# Power_supply.net
KiCad netlist of a schematic drawn in Altium Designer
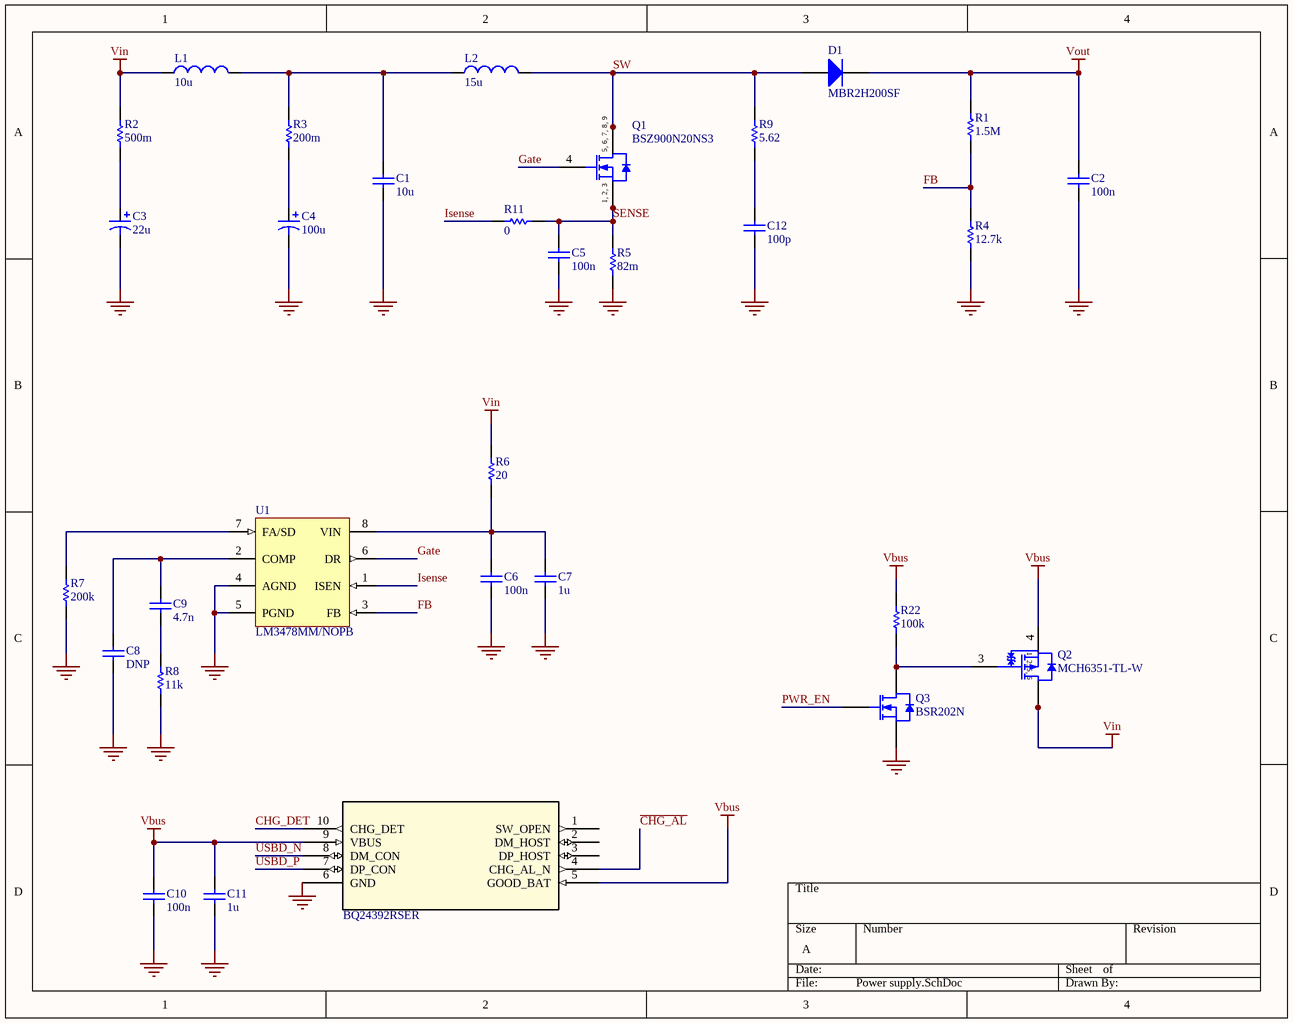
[diagram p0: Power supply.SchDoc]

(export (version "E")
  (design (tool "Eeschema 10.0.6"))
  (components
    (comp (ref "C1")
      (value "10u")
      (footprint "CAPC1206(3216)190_N")
      (description "CAP CER 10UF 25V X7R 1206")
      (fields
        (field (name "MANUFACTURER") "TDK Corporation")
        (field (name "MANUFACTURER PART NUMBER") "C3216X7R1E106K160AB")
      )
      (libsource (lib "Misc Caps") (part "C3216X7R1E106K160AB"))
    )
    (comp (ref "C2")
      (value "100n")
      (footprint "CAPC1812(4532)230_N")
      (fields
        (field (name "MANUFACTURER") "KEMET")
        (field (name "MANUFACTURER PART NUMBER") "C1812C104J2GACAUTO")
        (field (name "TOLERANCE") "5%")
      )
      (libsource (lib "Misc Caps") (part "C1812C104J2GACAUTO"))
    )
    (comp (ref "C3")
      (value "22u")
      (footprint "KEMET A")
      (description "CAP TANT POLY 22UF 6.3V 1206")
      (libsource (lib "Misc Caps") (part "T520A226M006ATE100"))
    )
    (comp (ref "C4")
      (value "100u")
      (footprint "KEMET A")
      (description "POLY TA SMD 3216 100UF 6.3V 20%")
      (libsource (lib "Misc Caps") (part "T520A107M006ATE045"))
    )
    (comp (ref "C5")
      (value "100n")
      (footprint "CAPC0603(1608)100_N")
      (description "CAP CER 0.1UF 10V X7R 0603")
      (fields
        (field (name "MANUFACTURER") "KEMET")
        (field (name "MANUFACTURER PART NUMBER") "C0603C104K8RACTU")
      )
      (libsource (lib "0603 Caps") (part "C0603C104K8RACTU"))
    )
    (comp (ref "C6")
      (value "100n")
      (footprint "CAPC0402(1005)33_N")
      (description "CAP CER 0.1UF 25V X7R 0402")
      (fields
        (field (name "MANUFACTURER") "Yageo")
        (field (name "MANUFACTURER PART NUMBER") "CC0402KRX7R8BB104")
      )
      (libsource (lib "0402 Caps") (part "CC0402KRX7R8BB104"))
    )
    (comp (ref "C7")
      (value "1u")
      (footprint "CAPC0402(1005)33_N")
      (description "CAP CER 1UF 25V X5R 0402")
      (libsource (lib "0402 Caps") (part "CGB2A1X5R1E105K033BC"))
    )
    (comp (ref "C8")
      (value "DNP")
      (footprint "CAPC0603(1608)100_N")
      (libsource (lib "0402 Caps") (part "0402 DNP JUMPER"))
    )
    (comp (ref "C9")
      (value "4.7n")
      (footprint "CAPC0603(1608)100_N")
      (description "CAP CER 4700PF 50V C0G 0603")
      (libsource (lib "0603 Caps") (part "C1608C0G1H472J080AA"))
    )
    (comp (ref "C10")
      (value "100n")
      (footprint "CAPC0402(1005)33_N")
      (description "CAP CER 0.1UF 25V X7R 0402")
      (fields
        (field (name "MANUFACTURER") "Yageo")
        (field (name "MANUFACTURER PART NUMBER") "CC0402KRX7R8BB104")
      )
      (libsource (lib "0402 Caps") (part "CC0402KRX7R8BB104"))
    )
    (comp (ref "C11")
      (value "1u")
      (footprint "CAPC0402(1005)33_N")
      (description "CAP CER 1UF 25V X5R 0402")
      (libsource (lib "0402 Caps") (part "CGB2A1X5R1E105K033BC"))
    )
    (comp (ref "C12")
      (value "100p")
      (footprint "CAPC0603(1608)100_N")
      (description "CAP CER 100PF 250V C0G/NP0 0603")
      (fields
        (field (name "MANUFACTURER") "KEMET")
        (field (name "MANUFACTURER PART NUMBER") "C0603C101JAGACTU")
      )
      (libsource (lib "0603 Caps") (part "C0603C101JAGACTU"))
    )
    (comp (ref "D1")
      (value "MBR2H200SF")
      (footprint "SOD-123FL")
      (description "DIODE SCHOTTKY 200V 2A SOD123")
      (fields
        (field (name "MANUFACTURER") "ON Semiconductor")
        (field (name "MANUFACTURER PART NUMBER") "MBR2H200SFT3G")
      )
      (libsource (lib "Discretes") (part "MBR2H200SF"))
    )
    (comp (ref "L1")
      (value "10u")
      (footprint "VLS6045EX")
      (description "FIXED IND 10UH 3.4A 61 MOHM SMD")
      (libsource (lib "Magnetics") (part "VLS6045EX-100M"))
    )
    (comp (ref "L2")
      (value "15u")
      (footprint "SRU8043")
      (description "FIXED IND 15UH 2.7A 46 MOHM SMD")
      (fields (field (name "MANUFACTURER") "Bourns") (field (name "MANUFACTURER PART NUMBER") "SRU8043-150Y"))
      (libsource (lib "Magnetics") (part "SRU8043-150Y"))
    )
    (comp (ref "Q1")
      (value "BSZ900N20NS3")
      (footprint "PG-TSDSON-8")
      (description "Trans MOSFET N-CH 200V 15.2A 8-Pin TSDSON")
      (fields
        (field (name "MANUFACTURER") "Infineon")
        (field (name "MANUFACTURER PART NUMBER") "BSZ900N20NS3GATMA1")
      )
      (libsource (lib "Discretes") (part "BSZ900N20NS3GATMA1"))
    )
    (comp (ref "Q2")
      (value "MCH6351-TL-W")
      (footprint "SOT23-6P65_210X90L25X32")
      (description "MOSFET PCH 1.8V DRIVE SERIES")
      (fields (field (name "MANUFACTURER") "ON Semiconductor"))
      (libsource (lib "Discretes") (part "MCH6351-TL-W"))
    )
    (comp (ref "Q3")
      (value "BSR202N")
      (footprint "INF-PG-SC59_N")
      (description "Trans MOSFET N-CH 20V 3.8A 3-Pin SC-59 T/R")
      (fields
        (field (name "MANUFACTURER") "Infineon")
        (field (name "MANUFACTURER PART NUMBER") "BSR202NL6327HTSA1")
      )
      (libsource (lib "Discretes") (part "BSR202N"))
    )
    (comp (ref "R1")
      (value "1.5M")
      (footprint "RESC0805(2012)_N")
      (description "RES SMD 1.5M OHM 0.1% 1/10W 0805")
      (fields
        (field (name "MANUFACTURER") "TE Connectivity Passive Product")
        (field (name "MANUFACTURER PART NUMBER") "CPF0805B1M5E1")
      )
      (libsource (lib "0805 Resistors") (part "CPF0805B1M5E1"))
    )
    (comp (ref "R2")
      (value "500m")
      (footprint "RESC0402(1005)_N")
      (description "RES 0.5 OHM 1% 1/16W 0402")
      (fields
        (field (name "MANUFACTURER") "Yageo")
        (field (name "MANUFACTURER PART NUMBER") "RC0402FR-071RL")
      )
      (libsource (lib "0402 Resistors") (part "RL0402FR-070R5L"))
    )
    (comp (ref "R3")
      (value "200m")
      (footprint "RESC0402(1005)_N")
      (description "RES 0.22 OHM 1% 1/16W 0402")
      (fields
        (field (name "MANUFACTURER") "Yageo")
        (field (name "MANUFACTURER PART NUMBER") "RC0402FR-071RL")
      )
      (libsource (lib "0402 Resistors") (part "RL0402FR-070R22L"))
    )
    (comp (ref "R4")
      (value "12.7k")
      (footprint "RESC0805(2012)_N")
      (description "RES SMD 12.7K OHM 0.1% 1/8W 0805")
      (fields
        (field (name "MANUFACTURER") "Yageo")
        (field (name "MANUFACTURER PART NUMBER") "RT0805BRD0712K7L")
      )
      (libsource (lib "0805 Resistors") (part "RT0805BRD0712K7L"))
    )
    (comp (ref "R5")
      (value "82m")
      (footprint "RESC0603(1608)_N")
      (fields
        (field (name "MANUFACTURER") "Panasonic")
        (field (name "MANUFACTURER PART NUMBER") "ERJ-3BWFR082V")
        (field (name "TOLERANCE") "1%")
      )
      (libsource (lib "0603 Resistors") (part "ERJ-3BWFR082V"))
    )
    (comp (ref "R6")
      (value "20")
      (footprint "RESC0402(1005)_N")
      (description "RES SMD 20 OHM 1% 1/16W 0402")
      (fields
        (field (name "MANUFACTURER") "Yageo")
        (field (name "MANUFACTURER PART NUMBER") "RC0402FR-0720RL")
      )
      (libsource (lib "0402 Resistors") (part "RC0402FR-0720RL"))
    )
    (comp (ref "R7")
      (value "200k")
      (footprint "RESC0402(1005)_N")
      (description "RES SMD 200K OHM 1% 1/16W 0402")
      (fields
        (field (name "MANUFACTURER") "Yageo")
        (field (name "MANUFACTURER PART NUMBER") "RC0402FR-07200KL")
      )
      (libsource (lib "0402 Resistors") (part "RC0402FR-07200KL"))
    )
    (comp (ref "R8")
      (value "11k")
      (footprint "RESC0402(1005)_N")
      (description "RES SMD 11K OHM 1% 1/16W 0402")
      (fields
        (field (name "MANUFACTURER") "Yageo")
        (field (name "MANUFACTURER PART NUMBER") "RC0402FR-0711KL")
      )
      (libsource (lib "0402 Resistors") (part "RC0402FR-0711KL"))
    )
    (comp (ref "R9")
      (value "5.62")
      (footprint "RESC0603(1608)_N")
      (description "RES SMD 5.62 OHM 1% 1/10W 0603")
      (fields
        (field (name "MANUFACTURER") "Vishay Dale")
        (field (name "MANUFACTURER PART NUMBER") "CRCW06035R62FKEA")
      )
      (libsource (lib "0603 Resistors") (part "CRCW06035R62FKEA"))
    )
    (comp (ref "R11")
      (value "0")
      (footprint "RESC0402(1005)_N")
      (description "RES SMD 0 OHM JUMPER 1/16W 0402")
      (fields
        (field (name "MANUFACTURER") "Yageo")
        (field (name "MANUFACTURER PART NUMBER") "RC0402FR-070RL")
      )
      (libsource (lib "0402 Resistors") (part "RC0402FR-070RL"))
    )
    (comp (ref "R22")
      (value "100k")
      (footprint "RESC0402(1005)_N")
      (description "RES SMD 100K OHM 1% 1/16W 0402")
      (fields
        (field (name "MANUFACTURER") "Yageo")
        (field (name "MANUFACTURER PART NUMBER") "RC0402FR-07100KL")
      )
      (libsource (lib "0402 Resistors") (part "RC0402FR-07100KL"))
    )
    (comp (ref "U1")
      (value "LM3478MM/NOPB")
      (footprint "DGK0008A_N")
      (description "TEXAS INSTRUMENTS   LM3478MM/NOPB.   N-CHANNEL CONTROLLER, MSOP-8, FULL REEL")
      (fields (field (name "MANUFACTURER") "Texas Instruments"))
      (libsource (lib "IC") (part "LM3478MM/NOPB"))
    )
    (comp (ref "U2")
      (value "BQ24392RSER")
      (footprint "QFN50P200X150X60-10N")
      (description "SPST USB 2.0 High-Speed Switch With Battery Charging Detection")
      (libsource (lib "IC") (part "BQ24392RSER"))
    )
  )
  (nets
    (net (code "1") (name "/CHG_DET") (class "Default")
      (node (ref "U2") (pin "10") (pinfunction "CHG_DET_10") (pintype "output"))
    )
    (net (code "2") (name "/FB") (class "Default")
      (node (ref "R1") (pin "1") (pinfunction "1_1") (pintype "passive"))
      (node (ref "R4") (pin "2") (pinfunction "2_2") (pintype "passive"))
      (node (ref "U1") (pin "3") (pinfunction "FB_3") (pintype "input"))
    )
    (net (code "3") (name "/Gate") (class "Default")
      (node (ref "Q1") (pin "4") (pinfunction "GATE_4") (pintype "passive"))
      (node (ref "U1") (pin "6") (pinfunction "DR_6") (pintype "output"))
    )
    (net (code "4") (name "/Isense") (class "Default")
      (node (ref "R11") (pin "1") (pinfunction "1_1") (pintype "passive"))
      (node (ref "U1") (pin "1") (pinfunction "ISEN_1") (pintype "input"))
    )
    (net (code "5") (name "/PWR_EN") (class "Default")
      (node (ref "Q3") (pin "1") (pinfunction "GATE_1") (pintype "passive"))
    )
    (net (code "6") (name "/SENSE") (class "Default")
      (node (ref "C5") (pin "2") (pinfunction "2_2") (pintype "passive"))
      (node (ref "Q1") (pin "1") (pinfunction "SOURCE_1") (pintype "passive"))
      (node (ref "Q1") (pin "2") (pinfunction "SOURCE_2") (pintype "passive"))
      (node (ref "Q1") (pin "3") (pinfunction "SOURCE_3") (pintype "passive"))
      (node (ref "R11") (pin "2") (pinfunction "2_2") (pintype "passive"))
      (node (ref "R5") (pin "2") (pinfunction "2_2") (pintype "passive"))
    )
    (net (code "7") (name "/SW") (class "Default")
      (node (ref "D1") (pin "1") (pinfunction "A_1") (pintype "passive"))
      (node (ref "L2") (pin "2") (pinfunction "2_2") (pintype "passive"))
      (node (ref "Q1") (pin "5") (pinfunction "DRAIN_5") (pintype "passive"))
      (node (ref "Q1") (pin "6") (pinfunction "DRAIN_6") (pintype "passive"))
      (node (ref "Q1") (pin "7") (pinfunction "DRAIN_7") (pintype "passive"))
      (node (ref "Q1") (pin "8") (pinfunction "DRAIN_8") (pintype "passive"))
      (node (ref "Q1") (pin "9") (pinfunction "DRAIN_9") (pintype "passive"))
      (node (ref "R9") (pin "2") (pinfunction "2_2") (pintype "passive"))
    )
    (net (code "8") (name "/USBD_N") (class "Default")
      (node (ref "U2") (pin "8") (pinfunction "DM_CON_8") (pintype "bidirectional"))
    )
    (net (code "9") (name "/USBD_P") (class "Default")
      (node (ref "U2") (pin "7") (pinfunction "DP_CON_7") (pintype "bidirectional"))
    )
    (net (code "10") (name "/~{CHG_AL}") (class "Default")
      (node (ref "U2") (pin "4") (pinfunction "CHG_AL_N_4") (pintype "output"))
    )
    (net (code "11") (name "GND") (class "Default")
      (node (ref "C1") (pin "1") (pinfunction "1_1") (pintype "passive"))
      (node (ref "C10") (pin "1") (pinfunction "1_1") (pintype "passive"))
      (node (ref "C11") (pin "1") (pinfunction "1_1") (pintype "passive"))
      (node (ref "C12") (pin "1") (pinfunction "1_1") (pintype "passive"))
      (node (ref "C2") (pin "1") (pinfunction "1_1") (pintype "passive"))
      (node (ref "C3") (pin "2") (pinfunction "2_2") (pintype "passive"))
      (node (ref "C4") (pin "2") (pinfunction "2_2") (pintype "passive"))
      (node (ref "C5") (pin "1") (pinfunction "1_1") (pintype "passive"))
      (node (ref "C6") (pin "1") (pinfunction "1_1") (pintype "passive"))
      (node (ref "C7") (pin "1") (pinfunction "1_1") (pintype "passive"))
      (node (ref "C8") (pin "1") (pinfunction "1_1") (pintype "passive"))
      (node (ref "Q3") (pin "2") (pinfunction "SOURCE_2") (pintype "passive"))
      (node (ref "R4") (pin "1") (pinfunction "1_1") (pintype "passive"))
      (node (ref "R5") (pin "1") (pinfunction "1_1") (pintype "passive"))
      (node (ref "R7") (pin "1") (pinfunction "1_1") (pintype "passive"))
      (node (ref "R8") (pin "1") (pinfunction "1_1") (pintype "passive"))
      (node (ref "U1") (pin "4") (pinfunction "AGND_4") (pintype "power_in"))
      (node (ref "U1") (pin "5") (pinfunction "PGND_5") (pintype "power_in"))
      (node (ref "U2") (pin "6") (pinfunction "GND_6") (pintype "power_in"))
    )
    (net (code "12") (name "Net-(C1-Pad2)") (class "Default")
      (node (ref "C1") (pin "2") (pinfunction "2_2") (pintype "passive"))
      (node (ref "L1") (pin "2") (pinfunction "2_2") (pintype "passive"))
      (node (ref "L2") (pin "1") (pinfunction "1_1") (pintype "passive"))
      (node (ref "R3") (pin "2") (pinfunction "2_2") (pintype "passive"))
    )
    (net (code "13") (name "Net-(C3-Pad1)") (class "Default")
      (node (ref "C3") (pin "1") (pinfunction "1_1") (pintype "passive"))
      (node (ref "R2") (pin "1") (pinfunction "1_1") (pintype "passive"))
    )
    (net (code "14") (name "Net-(C4-Pad1)") (class "Default")
      (node (ref "C4") (pin "1") (pinfunction "1_1") (pintype "passive"))
      (node (ref "R3") (pin "1") (pinfunction "1_1") (pintype "passive"))
    )
    (net (code "15") (name "Net-(C9-Pad1)") (class "Default")
      (node (ref "C9") (pin "1") (pinfunction "1_1") (pintype "passive"))
      (node (ref "R8") (pin "2") (pinfunction "2_2") (pintype "passive"))
    )
    (net (code "16") (name "Net-(C12-Pad2)") (class "Default")
      (node (ref "C12") (pin "2") (pinfunction "2_2") (pintype "passive"))
      (node (ref "R9") (pin "1") (pinfunction "1_1") (pintype "passive"))
    )
    (net (code "17") (name "Net-(Q2-G)") (class "Default")
      (node (ref "Q2") (pin "3") (pinfunction "G_3") (pintype "passive"))
      (node (ref "Q3") (pin "3") (pinfunction "DRAIN_3") (pintype "passive"))
      (node (ref "R22") (pin "1") (pinfunction "1_1") (pintype "passive"))
    )
    (net (code "18") (name "Net-(U1-COMP)") (class "Default")
      (node (ref "C8") (pin "2") (pinfunction "2_2") (pintype "passive"))
      (node (ref "C9") (pin "2") (pinfunction "2_2") (pintype "passive"))
      (node (ref "U1") (pin "2") (pinfunction "COMP_2") (pintype "passive"))
    )
    (net (code "19") (name "Net-(U1-FA{slash}SD)") (class "Default")
      (node (ref "R7") (pin "2") (pinfunction "2_2") (pintype "passive"))
      (node (ref "U1") (pin "7") (pinfunction "FA/SD_7") (pintype "input"))
    )
    (net (code "20") (name "Net-(U1-VIN)") (class "Default")
      (node (ref "C6") (pin "2") (pinfunction "2_2") (pintype "passive"))
      (node (ref "C7") (pin "2") (pinfunction "2_2") (pintype "passive"))
      (node (ref "R6") (pin "1") (pinfunction "1_1") (pintype "passive"))
      (node (ref "U1") (pin "8") (pinfunction "VIN_8") (pintype "power_in"))
    )
    (net (code "21") (name "Vbus") (class "Default")
      (node (ref "C10") (pin "2") (pinfunction "2_2") (pintype "passive"))
      (node (ref "C11") (pin "2") (pinfunction "2_2") (pintype "passive"))
      (node (ref "Q2") (pin "4") (pinfunction "S_4") (pintype "passive"))
      (node (ref "R22") (pin "2") (pinfunction "2_2") (pintype "passive"))
      (node (ref "U2") (pin "5") (pinfunction "GOOD_BAT_5") (pintype "input"))
      (node (ref "U2") (pin "9") (pinfunction "VBUS_9") (pintype "input"))
    )
    (net (code "22") (name "Vin") (class "Default")
      (node (ref "L1") (pin "1") (pinfunction "1_1") (pintype "passive"))
      (node (ref "Q2") (pin "1") (pinfunction "D_1") (pintype "passive"))
      (node (ref "Q2") (pin "2") (pinfunction "D_2") (pintype "passive"))
      (node (ref "Q2") (pin "5") (pinfunction "D_5") (pintype "passive"))
      (node (ref "Q2") (pin "6") (pinfunction "D_6") (pintype "passive"))
      (node (ref "R2") (pin "2") (pinfunction "2_2") (pintype "passive"))
      (node (ref "R6") (pin "2") (pinfunction "2_2") (pintype "passive"))
    )
    (net (code "23") (name "Vout") (class "Default")
      (node (ref "C2") (pin "2") (pinfunction "2_2") (pintype "passive"))
      (node (ref "D1") (pin "2") (pinfunction "K_2") (pintype "passive"))
      (node (ref "R1") (pin "2") (pinfunction "2_2") (pintype "passive"))
    )
    (net (code "24") (name "unconnected-(U2-DM_HOST-Pad2)") (class "Default")
      (node (ref "U2") (pin "2") (pinfunction "DM_HOST_2") (pintype "bidirectional"))
    )
    (net (code "25") (name "unconnected-(U2-DP_HOST-Pad3)") (class "Default")
      (node (ref "U2") (pin "3") (pinfunction "DP_HOST_3") (pintype "bidirectional"))
    )
    (net (code "26") (name "unconnected-(U2-SW_OPEN-Pad1)") (class "Default")
      (node (ref "U2") (pin "1") (pinfunction "SW_OPEN_1") (pintype "output"))
    )
  )
)
